# LiDAR.net
KiCad netlist of a schematic drawn in EAGLE
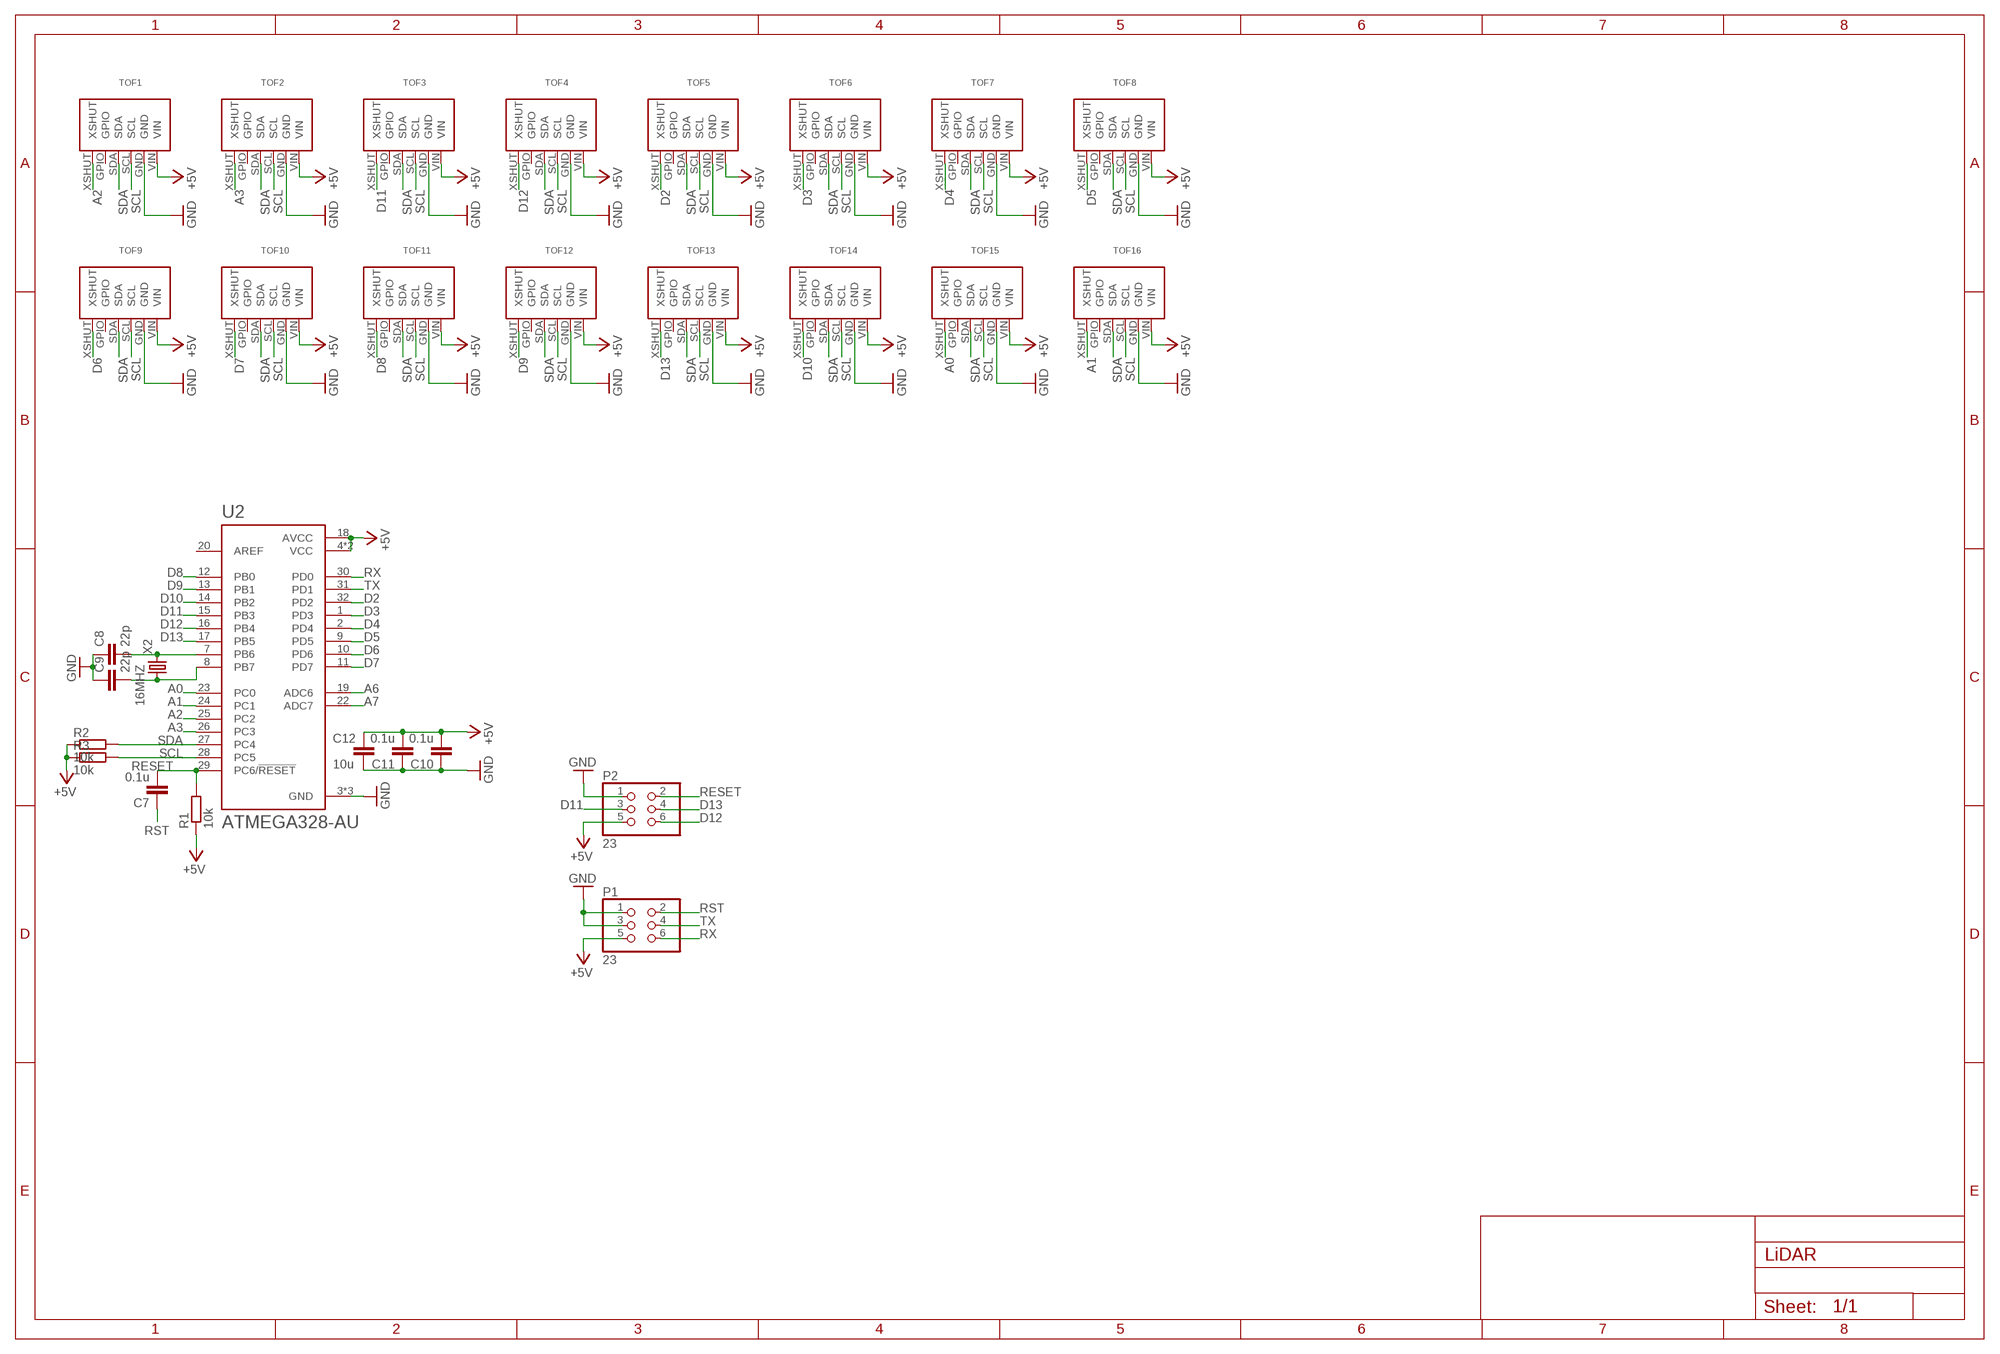
[diagram p0: schematic, sheet 1]

(export (version "E")
  (design (tool "Eeschema 10.0.6"))
  (components
    (comp (ref "C7")
      (value "0.1u")
      (footprint "eagle-import:C0603")
      (libsource (lib "eagle-import") (part "C-EUC0603"))
    )
    (comp (ref "C8")
      (value "22p")
      (footprint "eagle-import:C0603")
      (libsource (lib "eagle-import") (part "C-EUC0603"))
    )
    (comp (ref "C9")
      (value "22p")
      (footprint "eagle-import:C0603")
      (libsource (lib "eagle-import") (part "C-EUC0603"))
    )
    (comp (ref "C10")
      (value "0.1u")
      (footprint "eagle-import:C0603")
      (libsource (lib "eagle-import") (part "C-EUC0603"))
    )
    (comp (ref "C11")
      (value "0.1u")
      (footprint "eagle-import:C0603")
      (libsource (lib "eagle-import") (part "C-EUC0603"))
    )
    (comp (ref "C12")
      (value "10u")
      (footprint "eagle-import:C0805")
      (libsource (lib "eagle-import") (part "C-EUC0805"))
    )
    (comp (ref "P1") (value "23") (footprint "eagle-import:2_3") (libsource (lib "eagle-import") (part "23")))
    (comp (ref "P2") (value "23") (footprint "eagle-import:2_3") (libsource (lib "eagle-import") (part "23")))
    (comp (ref "R1")
      (value "10k")
      (footprint "eagle-import:0204_7")
      (libsource (lib "eagle-import") (part "R-EU_0204/7"))
    )
    (comp (ref "R2")
      (value "10k")
      (footprint "eagle-import:0204_7")
      (libsource (lib "eagle-import") (part "R-EU_0204/7"))
    )
    (comp (ref "R3")
      (value "10k")
      (footprint "eagle-import:0204_7")
      (libsource (lib "eagle-import") (part "R-EU_0204/7"))
    )
    (comp (ref "TOF1")
      (value "VL53L0X")
      (footprint "eagle-import:VL53L0X")
      (libsource (lib "eagle-import") (part "VL53L0X"))
    )
    (comp (ref "TOF2")
      (value "VL53L0X")
      (footprint "eagle-import:VL53L0X")
      (libsource (lib "eagle-import") (part "VL53L0X"))
    )
    (comp (ref "TOF3")
      (value "VL53L0X")
      (footprint "eagle-import:VL53L0X")
      (libsource (lib "eagle-import") (part "VL53L0X"))
    )
    (comp (ref "TOF4")
      (value "VL53L0X")
      (footprint "eagle-import:VL53L0X")
      (libsource (lib "eagle-import") (part "VL53L0X"))
    )
    (comp (ref "TOF5")
      (value "VL53L0X")
      (footprint "eagle-import:VL53L0X")
      (libsource (lib "eagle-import") (part "VL53L0X"))
    )
    (comp (ref "TOF6")
      (value "VL53L0X")
      (footprint "eagle-import:VL53L0X")
      (libsource (lib "eagle-import") (part "VL53L0X"))
    )
    (comp (ref "TOF7")
      (value "VL53L0X")
      (footprint "eagle-import:VL53L0X")
      (libsource (lib "eagle-import") (part "VL53L0X"))
    )
    (comp (ref "TOF8")
      (value "VL53L0X")
      (footprint "eagle-import:VL53L0X")
      (libsource (lib "eagle-import") (part "VL53L0X"))
    )
    (comp (ref "TOF9")
      (value "VL53L0X")
      (footprint "eagle-import:VL53L0X")
      (libsource (lib "eagle-import") (part "VL53L0X"))
    )
    (comp (ref "TOF10")
      (value "VL53L0X")
      (footprint "eagle-import:VL53L0X")
      (libsource (lib "eagle-import") (part "VL53L0X"))
    )
    (comp (ref "TOF11")
      (value "VL53L0X")
      (footprint "eagle-import:VL53L0X")
      (libsource (lib "eagle-import") (part "VL53L0X"))
    )
    (comp (ref "TOF12")
      (value "VL53L0X")
      (footprint "eagle-import:VL53L0X")
      (libsource (lib "eagle-import") (part "VL53L0X"))
    )
    (comp (ref "TOF13")
      (value "VL53L0X")
      (footprint "eagle-import:VL53L0X")
      (libsource (lib "eagle-import") (part "VL53L0X"))
    )
    (comp (ref "TOF14")
      (value "VL53L0X")
      (footprint "eagle-import:VL53L0X")
      (libsource (lib "eagle-import") (part "VL53L0X"))
    )
    (comp (ref "TOF15")
      (value "VL53L0X")
      (footprint "eagle-import:VL53L0X")
      (libsource (lib "eagle-import") (part "VL53L0X"))
    )
    (comp (ref "TOF16")
      (value "VL53L0X")
      (footprint "eagle-import:VL53L0X")
      (libsource (lib "eagle-import") (part "VL53L0X"))
    )
    (comp (ref "U2")
      (value "ATMEGA328-AU")
      (footprint "eagle-import:QFP80P900X900X120-32N")
      (fields (field (name "MF") "Microchip"))
      (libsource (lib "eagle-import") (part "ATMEGA328-AU"))
    )
    (comp (ref "X2")
      (value "16MHZ")
      (footprint "eagle-import:16MHZ")
      (libsource (lib "eagle-import") (part "16MHZ"))
    )
  )
  (nets
    (net (code "1") (name "+5V") (class "Default")
      (node (ref "C10") (pin "2") (pinfunction "2_2") (pintype "passive"))
      (node (ref "C11") (pin "2") (pinfunction "2_2") (pintype "passive"))
      (node (ref "C12") (pin "1") (pinfunction "1_1") (pintype "passive"))
      (node (ref "P1") (pin "5") (pinfunction "5_5") (pintype "passive"))
      (node (ref "P2") (pin "5") (pinfunction "5_5") (pintype "passive"))
      (node (ref "R1") (pin "1") (pinfunction "1_1") (pintype "passive"))
      (node (ref "R2") (pin "1") (pinfunction "1_1") (pintype "passive"))
      (node (ref "R3") (pin "1") (pinfunction "1_1") (pintype "passive"))
      (node (ref "TOF1") (pin "VIN") (pinfunction "VIN_VIN") (pintype "bidirectional"))
      (node (ref "TOF10") (pin "VIN") (pinfunction "VIN_VIN") (pintype "bidirectional"))
      (node (ref "TOF11") (pin "VIN") (pinfunction "VIN_VIN") (pintype "bidirectional"))
      (node (ref "TOF12") (pin "VIN") (pinfunction "VIN_VIN") (pintype "bidirectional"))
      (node (ref "TOF13") (pin "VIN") (pinfunction "VIN_VIN") (pintype "bidirectional"))
      (node (ref "TOF14") (pin "VIN") (pinfunction "VIN_VIN") (pintype "bidirectional"))
      (node (ref "TOF15") (pin "VIN") (pinfunction "VIN_VIN") (pintype "bidirectional"))
      (node (ref "TOF16") (pin "VIN") (pinfunction "VIN_VIN") (pintype "bidirectional"))
      (node (ref "TOF2") (pin "VIN") (pinfunction "VIN_VIN") (pintype "bidirectional"))
      (node (ref "TOF3") (pin "VIN") (pinfunction "VIN_VIN") (pintype "bidirectional"))
      (node (ref "TOF4") (pin "VIN") (pinfunction "VIN_VIN") (pintype "bidirectional"))
      (node (ref "TOF5") (pin "VIN") (pinfunction "VIN_VIN") (pintype "bidirectional"))
      (node (ref "TOF6") (pin "VIN") (pinfunction "VIN_VIN") (pintype "bidirectional"))
      (node (ref "TOF7") (pin "VIN") (pinfunction "VIN_VIN") (pintype "bidirectional"))
      (node (ref "TOF8") (pin "VIN") (pinfunction "VIN_VIN") (pintype "bidirectional"))
      (node (ref "TOF9") (pin "VIN") (pinfunction "VIN_VIN") (pintype "bidirectional"))
      (node (ref "U2") (pin "18") (pinfunction "AVCC_18") (pintype "power_in"))
      (node (ref "U2") (pin "4") (pinfunction "VCC_4") (pintype "power_in"))
      (node (ref "U2") (pin "6") (pinfunction "VCC_6") (pintype "power_in"))
    )
    (net (code "2") (name "/A0") (class "Default")
      (node (ref "TOF15") (pin "XSHUT") (pinfunction "XSHUT_XSHUT") (pintype "bidirectional"))
      (node (ref "U2") (pin "23") (pinfunction "PC0_23") (pintype "bidirectional"))
    )
    (net (code "3") (name "/A1") (class "Default")
      (node (ref "TOF16") (pin "XSHUT") (pinfunction "XSHUT_XSHUT") (pintype "bidirectional"))
      (node (ref "U2") (pin "24") (pinfunction "PC1_24") (pintype "bidirectional"))
    )
    (net (code "4") (name "/A2") (class "Default")
      (node (ref "TOF1") (pin "XSHUT") (pinfunction "XSHUT_XSHUT") (pintype "bidirectional"))
      (node (ref "U2") (pin "25") (pinfunction "PC2_25") (pintype "bidirectional"))
    )
    (net (code "5") (name "/A3") (class "Default")
      (node (ref "TOF2") (pin "XSHUT") (pinfunction "XSHUT_XSHUT") (pintype "bidirectional"))
      (node (ref "U2") (pin "26") (pinfunction "PC3_26") (pintype "bidirectional"))
    )
    (net (code "6") (name "/A6") (class "Default")
      (node (ref "U2") (pin "19") (pinfunction "ADC6_19") (pintype "bidirectional"))
    )
    (net (code "7") (name "/A7") (class "Default")
      (node (ref "U2") (pin "22") (pinfunction "ADC7_22") (pintype "bidirectional"))
    )
    (net (code "8") (name "/D2") (class "Default")
      (node (ref "TOF5") (pin "XSHUT") (pinfunction "XSHUT_XSHUT") (pintype "bidirectional"))
      (node (ref "U2") (pin "32") (pinfunction "PD2_32") (pintype "bidirectional"))
    )
    (net (code "9") (name "/D3") (class "Default")
      (node (ref "TOF6") (pin "XSHUT") (pinfunction "XSHUT_XSHUT") (pintype "bidirectional"))
      (node (ref "U2") (pin "1") (pinfunction "PD3_1") (pintype "bidirectional"))
    )
    (net (code "10") (name "/D4") (class "Default")
      (node (ref "TOF7") (pin "XSHUT") (pinfunction "XSHUT_XSHUT") (pintype "bidirectional"))
      (node (ref "U2") (pin "2") (pinfunction "PD4_2") (pintype "bidirectional"))
    )
    (net (code "11") (name "/D5") (class "Default")
      (node (ref "TOF8") (pin "XSHUT") (pinfunction "XSHUT_XSHUT") (pintype "bidirectional"))
      (node (ref "U2") (pin "9") (pinfunction "PD5_9") (pintype "bidirectional"))
    )
    (net (code "12") (name "/D6") (class "Default")
      (node (ref "TOF9") (pin "XSHUT") (pinfunction "XSHUT_XSHUT") (pintype "bidirectional"))
      (node (ref "U2") (pin "10") (pinfunction "PD6_10") (pintype "bidirectional"))
    )
    (net (code "13") (name "/D7") (class "Default")
      (node (ref "TOF10") (pin "XSHUT") (pinfunction "XSHUT_XSHUT") (pintype "bidirectional"))
      (node (ref "U2") (pin "11") (pinfunction "PD7_11") (pintype "bidirectional"))
    )
    (net (code "14") (name "/D8") (class "Default")
      (node (ref "TOF11") (pin "XSHUT") (pinfunction "XSHUT_XSHUT") (pintype "bidirectional"))
      (node (ref "U2") (pin "12") (pinfunction "PB0_12") (pintype "bidirectional"))
    )
    (net (code "15") (name "/D9") (class "Default")
      (node (ref "TOF12") (pin "XSHUT") (pinfunction "XSHUT_XSHUT") (pintype "bidirectional"))
      (node (ref "U2") (pin "13") (pinfunction "PB1_13") (pintype "bidirectional"))
    )
    (net (code "16") (name "/D10") (class "Default")
      (node (ref "TOF14") (pin "XSHUT") (pinfunction "XSHUT_XSHUT") (pintype "bidirectional"))
      (node (ref "U2") (pin "14") (pinfunction "PB2_14") (pintype "bidirectional"))
    )
    (net (code "17") (name "/D11") (class "Default")
      (node (ref "P2") (pin "3") (pinfunction "3_3") (pintype "passive"))
      (node (ref "TOF3") (pin "XSHUT") (pinfunction "XSHUT_XSHUT") (pintype "bidirectional"))
      (node (ref "U2") (pin "15") (pinfunction "PB3_15") (pintype "bidirectional"))
    )
    (net (code "18") (name "/D12") (class "Default")
      (node (ref "P2") (pin "6") (pinfunction "6_6") (pintype "passive"))
      (node (ref "TOF4") (pin "XSHUT") (pinfunction "XSHUT_XSHUT") (pintype "bidirectional"))
      (node (ref "U2") (pin "16") (pinfunction "PB4_16") (pintype "bidirectional"))
    )
    (net (code "19") (name "/D13") (class "Default")
      (node (ref "P2") (pin "4") (pinfunction "4_4") (pintype "passive"))
      (node (ref "TOF13") (pin "XSHUT") (pinfunction "XSHUT_XSHUT") (pintype "bidirectional"))
      (node (ref "U2") (pin "17") (pinfunction "PB5_17") (pintype "bidirectional"))
    )
    (net (code "20") (name "/RESET") (class "Default")
      (node (ref "C7") (pin "2") (pinfunction "2_2") (pintype "passive"))
      (node (ref "P2") (pin "2") (pinfunction "2_2") (pintype "passive"))
      (node (ref "R1") (pin "2") (pinfunction "2_2") (pintype "passive"))
      (node (ref "U2") (pin "29") (pinfunction "PC6/~{RESET}_29") (pintype "bidirectional"))
    )
    (net (code "21") (name "/RST") (class "Default")
      (node (ref "C7") (pin "1") (pinfunction "1_1") (pintype "passive"))
      (node (ref "P1") (pin "2") (pinfunction "2_2") (pintype "passive"))
    )
    (net (code "22") (name "/RX") (class "Default")
      (node (ref "P1") (pin "6") (pinfunction "6_6") (pintype "passive"))
      (node (ref "U2") (pin "30") (pinfunction "PD0_30") (pintype "bidirectional"))
    )
    (net (code "23") (name "/SCL") (class "Default")
      (node (ref "R3") (pin "2") (pinfunction "2_2") (pintype "passive"))
      (node (ref "TOF1") (pin "SCL") (pinfunction "SCL_SCL") (pintype "bidirectional"))
      (node (ref "TOF10") (pin "SCL") (pinfunction "SCL_SCL") (pintype "bidirectional"))
      (node (ref "TOF11") (pin "SCL") (pinfunction "SCL_SCL") (pintype "bidirectional"))
      (node (ref "TOF12") (pin "SCL") (pinfunction "SCL_SCL") (pintype "bidirectional"))
      (node (ref "TOF13") (pin "SCL") (pinfunction "SCL_SCL") (pintype "bidirectional"))
      (node (ref "TOF14") (pin "SCL") (pinfunction "SCL_SCL") (pintype "bidirectional"))
      (node (ref "TOF15") (pin "SCL") (pinfunction "SCL_SCL") (pintype "bidirectional"))
      (node (ref "TOF16") (pin "SCL") (pinfunction "SCL_SCL") (pintype "bidirectional"))
      (node (ref "TOF2") (pin "SCL") (pinfunction "SCL_SCL") (pintype "bidirectional"))
      (node (ref "TOF3") (pin "SCL") (pinfunction "SCL_SCL") (pintype "bidirectional"))
      (node (ref "TOF4") (pin "SCL") (pinfunction "SCL_SCL") (pintype "bidirectional"))
      (node (ref "TOF5") (pin "SCL") (pinfunction "SCL_SCL") (pintype "bidirectional"))
      (node (ref "TOF6") (pin "SCL") (pinfunction "SCL_SCL") (pintype "bidirectional"))
      (node (ref "TOF7") (pin "SCL") (pinfunction "SCL_SCL") (pintype "bidirectional"))
      (node (ref "TOF8") (pin "SCL") (pinfunction "SCL_SCL") (pintype "bidirectional"))
      (node (ref "TOF9") (pin "SCL") (pinfunction "SCL_SCL") (pintype "bidirectional"))
      (node (ref "U2") (pin "28") (pinfunction "PC5_28") (pintype "bidirectional"))
    )
    (net (code "24") (name "/SDA") (class "Default")
      (node (ref "R2") (pin "2") (pinfunction "2_2") (pintype "passive"))
      (node (ref "TOF1") (pin "SDA") (pinfunction "SDA_SDA") (pintype "bidirectional"))
      (node (ref "TOF10") (pin "SDA") (pinfunction "SDA_SDA") (pintype "bidirectional"))
      (node (ref "TOF11") (pin "SDA") (pinfunction "SDA_SDA") (pintype "bidirectional"))
      (node (ref "TOF12") (pin "SDA") (pinfunction "SDA_SDA") (pintype "bidirectional"))
      (node (ref "TOF13") (pin "SDA") (pinfunction "SDA_SDA") (pintype "bidirectional"))
      (node (ref "TOF14") (pin "SDA") (pinfunction "SDA_SDA") (pintype "bidirectional"))
      (node (ref "TOF15") (pin "SDA") (pinfunction "SDA_SDA") (pintype "bidirectional"))
      (node (ref "TOF16") (pin "SDA") (pinfunction "SDA_SDA") (pintype "bidirectional"))
      (node (ref "TOF2") (pin "SDA") (pinfunction "SDA_SDA") (pintype "bidirectional"))
      (node (ref "TOF3") (pin "SDA") (pinfunction "SDA_SDA") (pintype "bidirectional"))
      (node (ref "TOF4") (pin "SDA") (pinfunction "SDA_SDA") (pintype "bidirectional"))
      (node (ref "TOF5") (pin "SDA") (pinfunction "SDA_SDA") (pintype "bidirectional"))
      (node (ref "TOF6") (pin "SDA") (pinfunction "SDA_SDA") (pintype "bidirectional"))
      (node (ref "TOF7") (pin "SDA") (pinfunction "SDA_SDA") (pintype "bidirectional"))
      (node (ref "TOF8") (pin "SDA") (pinfunction "SDA_SDA") (pintype "bidirectional"))
      (node (ref "TOF9") (pin "SDA") (pinfunction "SDA_SDA") (pintype "bidirectional"))
      (node (ref "U2") (pin "27") (pinfunction "PC4_27") (pintype "bidirectional"))
    )
    (net (code "25") (name "/TX") (class "Default")
      (node (ref "P1") (pin "4") (pinfunction "4_4") (pintype "passive"))
      (node (ref "U2") (pin "31") (pinfunction "PD1_31") (pintype "bidirectional"))
    )
    (net (code "26") (name "GND") (class "Default")
      (node (ref "C10") (pin "1") (pinfunction "1_1") (pintype "passive"))
      (node (ref "C11") (pin "1") (pinfunction "1_1") (pintype "passive"))
      (node (ref "C12") (pin "2") (pinfunction "2_2") (pintype "passive"))
      (node (ref "C8") (pin "1") (pinfunction "1_1") (pintype "passive"))
      (node (ref "C9") (pin "1") (pinfunction "1_1") (pintype "passive"))
      (node (ref "P1") (pin "1") (pinfunction "1_1") (pintype "passive"))
      (node (ref "P1") (pin "3") (pinfunction "3_3") (pintype "passive"))
      (node (ref "P2") (pin "1") (pinfunction "1_1") (pintype "passive"))
      (node (ref "TOF1") (pin "GND") (pinfunction "GND_GND") (pintype "bidirectional"))
      (node (ref "TOF10") (pin "GND") (pinfunction "GND_GND") (pintype "bidirectional"))
      (node (ref "TOF11") (pin "GND") (pinfunction "GND_GND") (pintype "bidirectional"))
      (node (ref "TOF12") (pin "GND") (pinfunction "GND_GND") (pintype "bidirectional"))
      (node (ref "TOF13") (pin "GND") (pinfunction "GND_GND") (pintype "bidirectional"))
      (node (ref "TOF14") (pin "GND") (pinfunction "GND_GND") (pintype "bidirectional"))
      (node (ref "TOF15") (pin "GND") (pinfunction "GND_GND") (pintype "bidirectional"))
      (node (ref "TOF16") (pin "GND") (pinfunction "GND_GND") (pintype "bidirectional"))
      (node (ref "TOF2") (pin "GND") (pinfunction "GND_GND") (pintype "bidirectional"))
      (node (ref "TOF3") (pin "GND") (pinfunction "GND_GND") (pintype "bidirectional"))
      (node (ref "TOF4") (pin "GND") (pinfunction "GND_GND") (pintype "bidirectional"))
      (node (ref "TOF5") (pin "GND") (pinfunction "GND_GND") (pintype "bidirectional"))
      (node (ref "TOF6") (pin "GND") (pinfunction "GND_GND") (pintype "bidirectional"))
      (node (ref "TOF7") (pin "GND") (pinfunction "GND_GND") (pintype "bidirectional"))
      (node (ref "TOF8") (pin "GND") (pinfunction "GND_GND") (pintype "bidirectional"))
      (node (ref "TOF9") (pin "GND") (pinfunction "GND_GND") (pintype "bidirectional"))
      (node (ref "U2") (pin "21") (pinfunction "GND_21") (pintype "power_in"))
      (node (ref "U2") (pin "3") (pinfunction "GND_3") (pintype "power_in"))
      (node (ref "U2") (pin "5") (pinfunction "GND_5") (pintype "power_in"))
    )
    (net (code "27") (name "Net-(U2-PB6)") (class "Default")
      (node (ref "C8") (pin "2") (pinfunction "2_2") (pintype "passive"))
      (node (ref "U2") (pin "7") (pinfunction "PB6_7") (pintype "bidirectional"))
      (node (ref "X2") (pin "P$2") (pinfunction "2_P$2") (pintype "passive"))
    )
    (net (code "28") (name "Net-(U2-PB7)") (class "Default")
      (node (ref "C9") (pin "2") (pinfunction "2_2") (pintype "passive"))
      (node (ref "U2") (pin "8") (pinfunction "PB7_8") (pintype "bidirectional"))
      (node (ref "X2") (pin "P$1") (pinfunction "1_P$1") (pintype "passive"))
    )
    (net (code "29") (name "unconnected-(TOF1-PadGPIO)") (class "Default")
      (node (ref "TOF1") (pin "GPIO") (pinfunction "GPIO_GPIO") (pintype "bidirectional"))
    )
    (net (code "30") (name "unconnected-(TOF2-PadGPIO)") (class "Default")
      (node (ref "TOF2") (pin "GPIO") (pinfunction "GPIO_GPIO") (pintype "bidirectional"))
    )
    (net (code "31") (name "unconnected-(TOF3-PadGPIO)") (class "Default")
      (node (ref "TOF3") (pin "GPIO") (pinfunction "GPIO_GPIO") (pintype "bidirectional"))
    )
    (net (code "32") (name "unconnected-(TOF4-PadGPIO)") (class "Default")
      (node (ref "TOF4") (pin "GPIO") (pinfunction "GPIO_GPIO") (pintype "bidirectional"))
    )
    (net (code "33") (name "unconnected-(TOF5-PadGPIO)") (class "Default")
      (node (ref "TOF5") (pin "GPIO") (pinfunction "GPIO_GPIO") (pintype "bidirectional"))
    )
    (net (code "34") (name "unconnected-(TOF6-PadGPIO)") (class "Default")
      (node (ref "TOF6") (pin "GPIO") (pinfunction "GPIO_GPIO") (pintype "bidirectional"))
    )
    (net (code "35") (name "unconnected-(TOF7-PadGPIO)") (class "Default")
      (node (ref "TOF7") (pin "GPIO") (pinfunction "GPIO_GPIO") (pintype "bidirectional"))
    )
    (net (code "36") (name "unconnected-(TOF8-PadGPIO)") (class "Default")
      (node (ref "TOF8") (pin "GPIO") (pinfunction "GPIO_GPIO") (pintype "bidirectional"))
    )
    (net (code "37") (name "unconnected-(TOF9-PadGPIO)") (class "Default")
      (node (ref "TOF9") (pin "GPIO") (pinfunction "GPIO_GPIO") (pintype "bidirectional"))
    )
    (net (code "38") (name "unconnected-(TOF10-PadGPIO)") (class "Default")
      (node (ref "TOF10") (pin "GPIO") (pinfunction "GPIO_GPIO") (pintype "bidirectional"))
    )
    (net (code "39") (name "unconnected-(TOF11-PadGPIO)") (class "Default")
      (node (ref "TOF11") (pin "GPIO") (pinfunction "GPIO_GPIO") (pintype "bidirectional"))
    )
    (net (code "40") (name "unconnected-(TOF12-PadGPIO)") (class "Default")
      (node (ref "TOF12") (pin "GPIO") (pinfunction "GPIO_GPIO") (pintype "bidirectional"))
    )
    (net (code "41") (name "unconnected-(TOF13-PadGPIO)") (class "Default")
      (node (ref "TOF13") (pin "GPIO") (pinfunction "GPIO_GPIO") (pintype "bidirectional"))
    )
    (net (code "42") (name "unconnected-(TOF14-PadGPIO)") (class "Default")
      (node (ref "TOF14") (pin "GPIO") (pinfunction "GPIO_GPIO") (pintype "bidirectional"))
    )
    (net (code "43") (name "unconnected-(TOF15-PadGPIO)") (class "Default")
      (node (ref "TOF15") (pin "GPIO") (pinfunction "GPIO_GPIO") (pintype "bidirectional"))
    )
    (net (code "44") (name "unconnected-(TOF16-PadGPIO)") (class "Default")
      (node (ref "TOF16") (pin "GPIO") (pinfunction "GPIO_GPIO") (pintype "bidirectional"))
    )
    (net (code "45") (name "unconnected-(U2-AREF-Pad20)") (class "Default")
      (node (ref "U2") (pin "20") (pinfunction "AREF_20") (pintype "input"))
    )
  )
)
